# ESP32-EDU-BOARD_V0_1.net
KiCad netlist of a schematic drawn in EasyEDA
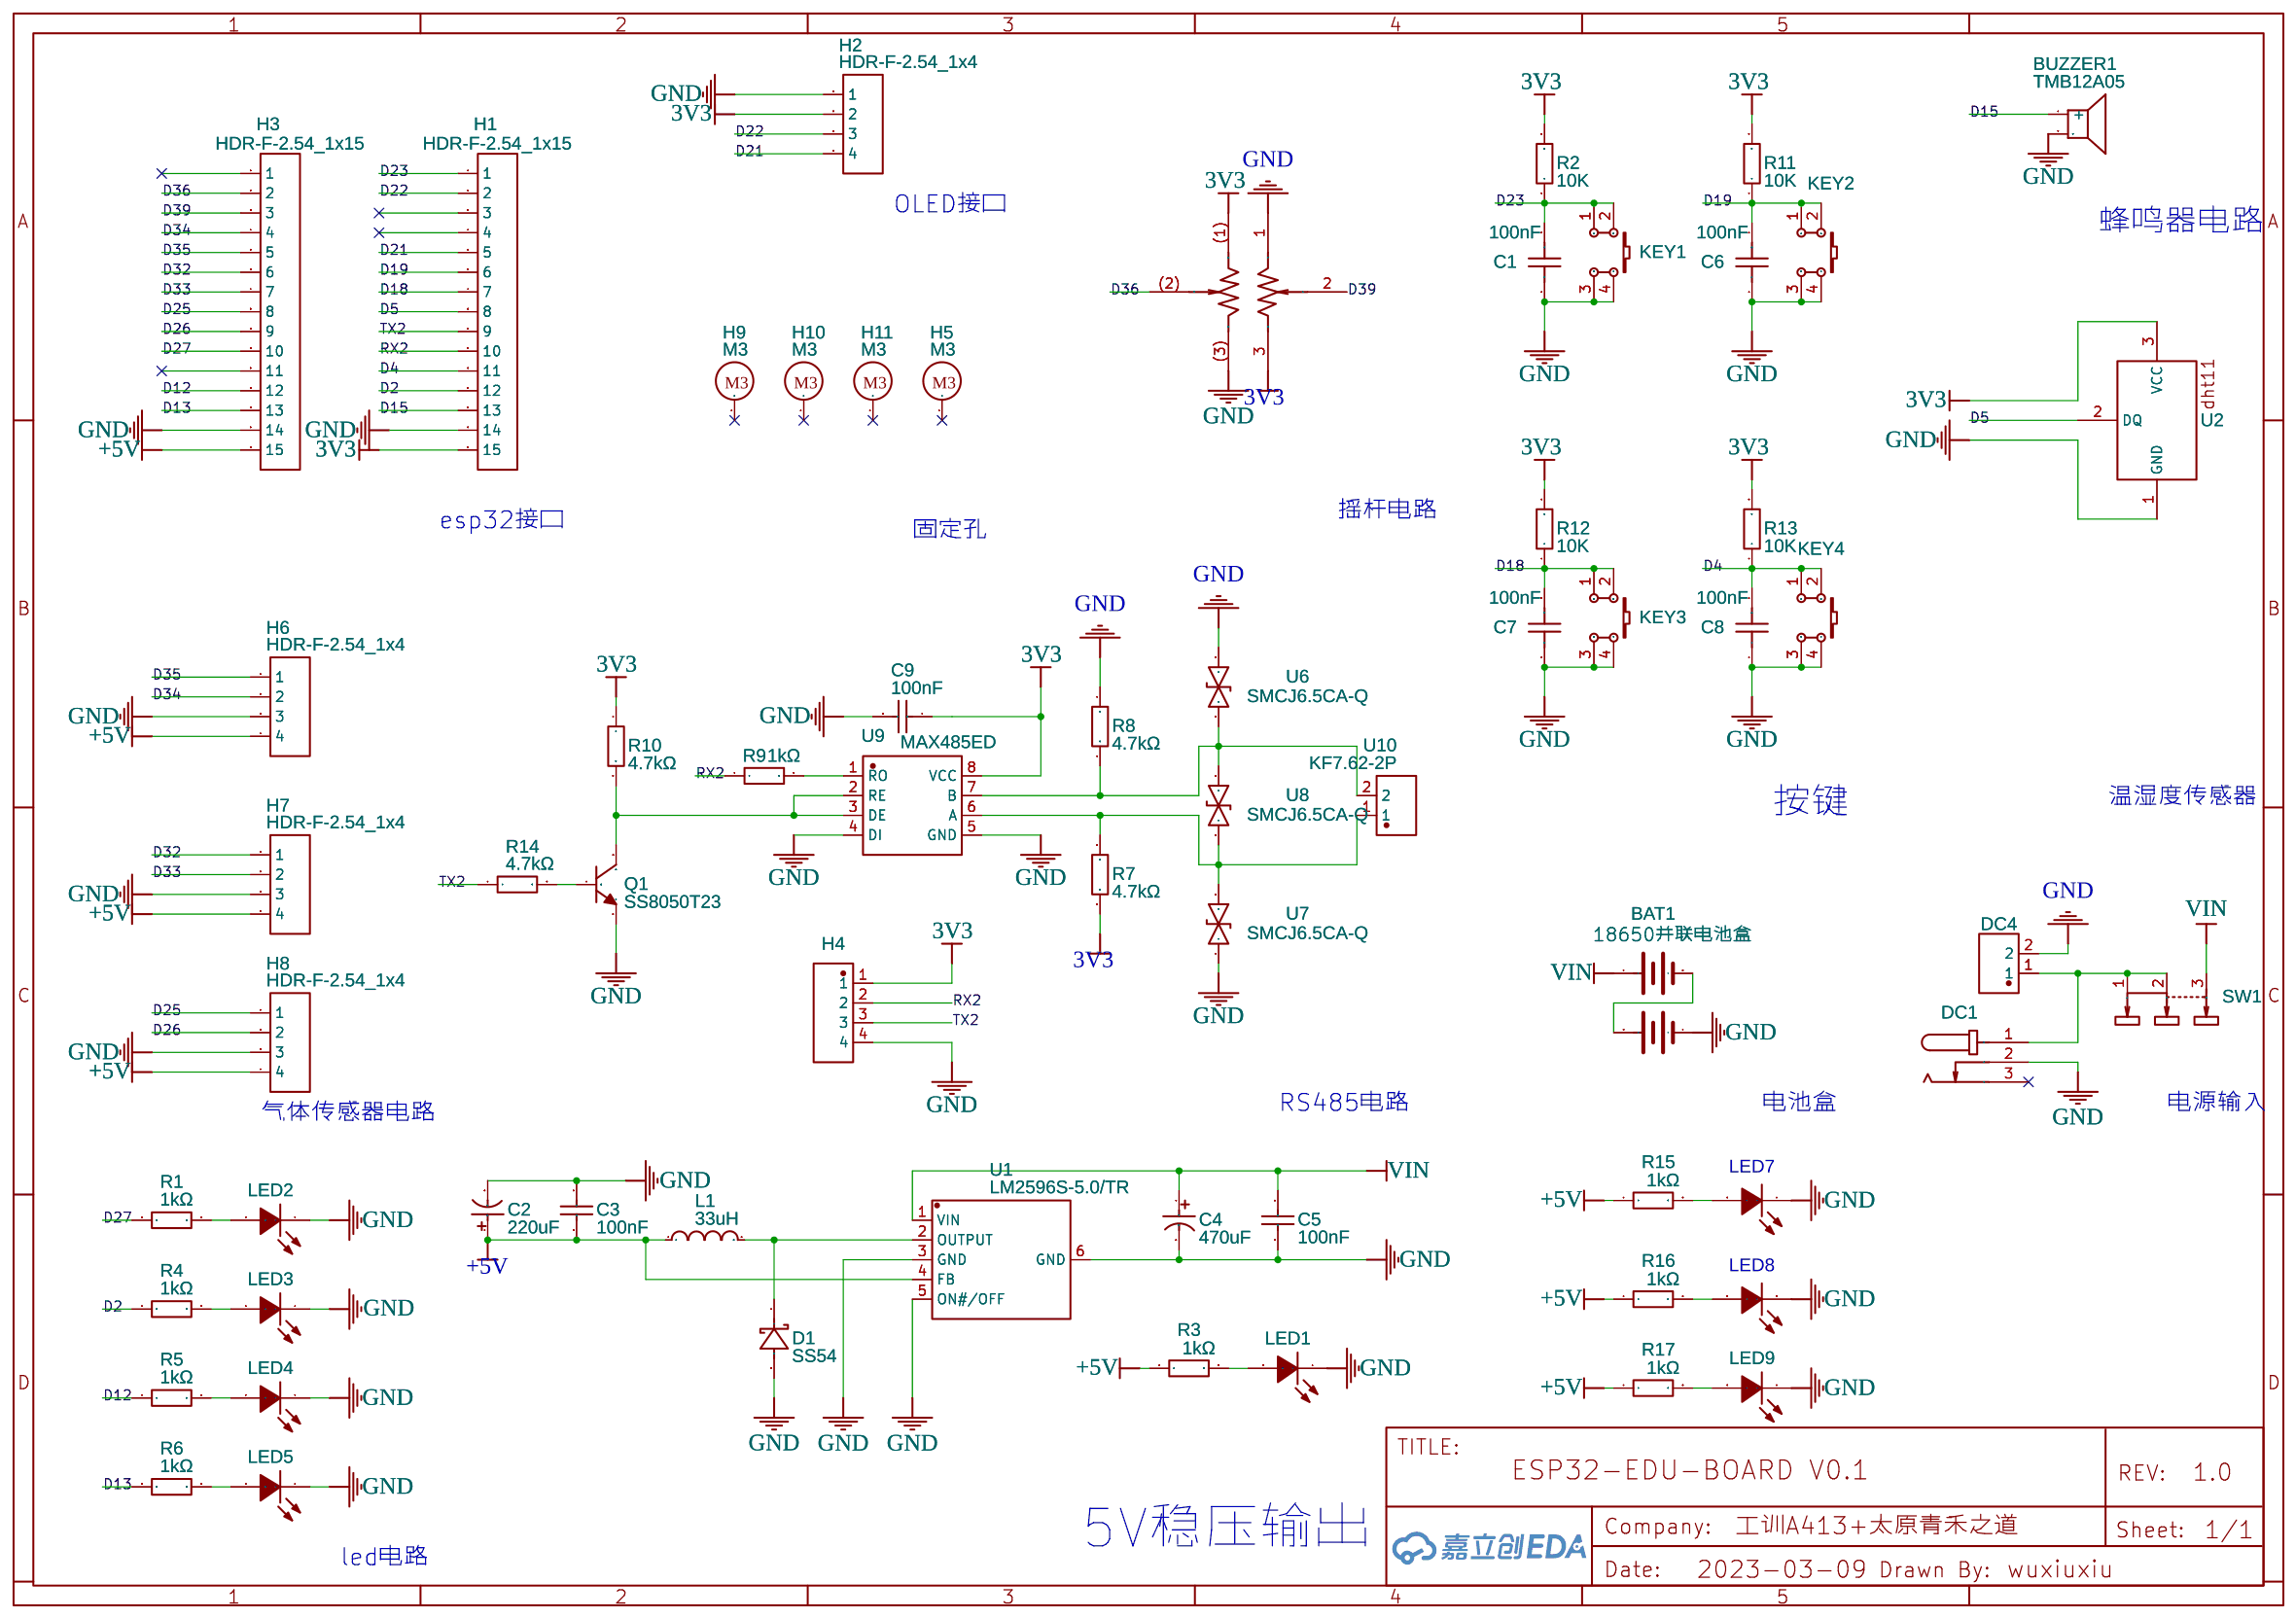
[diagram p0: schematic sheet]

(export (version "E")
  (design (tool "Eeschema 10.0.6"))
  (components
    (comp (ref "BAT1")
      (value "18650并联电池盒")
      (fields (field (name "BOM_Supplier Part") "C9900010344"))
      (libsource (lib "") (part "18650并联电池盒"))
    )
    (comp (ref "BUZZER1")
      (value "TMB12A05")
      (fields (field (name "BOM_Supplier Part") "C96093"))
      (libsource (lib "") (part "TMB12A05"))
    )
    (comp (ref "C1")
      (value "100nF")
      (fields
        (field (name "BOM_Manufacturer Part") "CC0603KRX7R9BB104")
        (field (name "BOM_Supplier Part") "C14663")
      )
      (libsource (lib "") (part "CC0603KRX7R9BB104"))
    )
    (comp (ref "C2")
      (value "220uF")
      (fields
        (field (name "BOM_Manufacturer Part") "RT1A221M0605")
        (field (name "BOM_Supplier Part") "C267466")
      )
      (libsource (lib "") (part "RT1A221M0605"))
    )
    (comp (ref "C3")
      (value "100nF")
      (fields
        (field (name "BOM_Manufacturer Part") "CL21B104KBCNNNC")
        (field (name "BOM_Supplier Part") "C1711")
      )
      (libsource (lib "") (part "CL21B104KBCNNNC_1"))
    )
    (comp (ref "C4")
      (value "470uF")
      (fields
        (field (name "BOM_Manufacturer Part") "RVE1C471M0810")
        (field (name "BOM_Supplier Part") "C107396")
      )
      (libsource (lib "") (part "RVE1C471M0810"))
    )
    (comp (ref "C5")
      (value "100nF")
      (fields
        (field (name "BOM_Manufacturer Part") "CL21B104KBCNNNC")
        (field (name "BOM_Supplier Part") "C1711")
      )
      (libsource (lib "") (part "CL21B104KBCNNNC_1"))
    )
    (comp (ref "C6")
      (value "100nF")
      (fields
        (field (name "BOM_Manufacturer Part") "CC0603KRX7R9BB104")
        (field (name "BOM_Supplier Part") "C14663")
      )
      (libsource (lib "") (part "CC0603KRX7R9BB104"))
    )
    (comp (ref "C7")
      (value "100nF")
      (fields
        (field (name "BOM_Manufacturer Part") "CC0603KRX7R9BB104")
        (field (name "BOM_Supplier Part") "C14663")
      )
      (libsource (lib "") (part "CC0603KRX7R9BB104"))
    )
    (comp (ref "C8")
      (value "100nF")
      (fields
        (field (name "BOM_Manufacturer Part") "CC0603KRX7R9BB104")
        (field (name "BOM_Supplier Part") "C14663")
      )
      (libsource (lib "") (part "CC0603KRX7R9BB104"))
    )
    (comp (ref "C9")
      (value "100nF")
      (fields
        (field (name "BOM_Manufacturer Part") "CL21B104KBCNNNC")
        (field (name "BOM_Supplier Part") "C1711")
      )
      (libsource (lib "") (part "CL21B104KBCNNNC"))
    )
    (comp (ref "D1")
      (value "SS54")
      (fields (field (name "BOM_Supplier Part") "C727065"))
      (libsource (lib "") (part "SS54_C727065"))
    )
    (comp (ref "DC1")
      (value "KH-DC-005-2.5")
      (fields (field (name "BOM_Supplier Part") "C2847170"))
      (libsource (lib "") (part "KH-DC-005-2.5"))
    )
    (comp (ref "DC4")
      (value "KF301-5.0-2P")
      (fields (field (name "BOM_Supplier Part") "C474881"))
      (libsource (lib "") (part "KF301-5.0-2P"))
    )
    (comp (ref "H1")
      (value "HDR-F-2.54_1x15")
      (fields (field (name "BOM_Supplier Part") "C124408"))
      (libsource (lib "") (part "HDR-F-2.54_1x15"))
    )
    (comp (ref "H2")
      (value "HDR-F-2.54_1x4")
      (fields (field (name "BOM_Supplier Part") "C225501"))
      (libsource (lib "") (part "HDR-F-2.54_1x4"))
    )
    (comp (ref "H3")
      (value "HDR-F-2.54_1x15")
      (fields (field (name "BOM_Supplier Part") "C124408"))
      (libsource (lib "") (part "HDR-F-2.54_1x15"))
    )
    (comp (ref "H4")
      (value "12251104CNSNS295001")
      (fields (field (name "BOM_Supplier Part") "C355292"))
      (libsource (lib "") (part "12251104CNSNS295001"))
    )
    (comp (ref "H5") (value "M3") (libsource (lib "") (part "M3")))
    (comp (ref "H6")
      (value "HDR-F-2.54_1x4")
      (fields (field (name "BOM_Supplier Part") "C225501"))
      (libsource (lib "") (part "HDR-F-2.54_1x4"))
    )
    (comp (ref "H7")
      (value "HDR-F-2.54_1x4")
      (fields (field (name "BOM_Supplier Part") "C225501"))
      (libsource (lib "") (part "HDR-F-2.54_1x4"))
    )
    (comp (ref "H8")
      (value "HDR-F-2.54_1x4")
      (fields (field (name "BOM_Supplier Part") "C225501"))
      (libsource (lib "") (part "HDR-F-2.54_1x4"))
    )
    (comp (ref "H9") (value "M3") (libsource (lib "") (part "M3")))
    (comp (ref "H10") (value "M3") (libsource (lib "") (part "M3")))
    (comp (ref "H11") (value "M3") (libsource (lib "") (part "M3")))
    (comp (ref "KEY1")
      (value "K4-6×6_SMD")
      (fields
        (field (name "BOM_Manufacturer Part") "K2-6639SP-D4SC-04")
        (field (name "BOM_Supplier Part") "C191626")
      )
      (libsource (lib "") (part "K4-6×6_SMD"))
    )
    (comp (ref "KEY2")
      (value "K4-6×6_SMD")
      (fields
        (field (name "BOM_Manufacturer Part") "K2-6639SP-D4SC-04")
        (field (name "BOM_Supplier Part") "C191626")
      )
      (libsource (lib "") (part "K4-6×6_SMD"))
    )
    (comp (ref "KEY3")
      (value "K4-6×6_SMD")
      (fields
        (field (name "BOM_Manufacturer Part") "K2-6639SP-D4SC-04")
        (field (name "BOM_Supplier Part") "C191626")
      )
      (libsource (lib "") (part "K4-6×6_SMD"))
    )
    (comp (ref "KEY4")
      (value "K4-6×6_SMD")
      (fields
        (field (name "BOM_Manufacturer Part") "K2-6639SP-D4SC-04")
        (field (name "BOM_Supplier Part") "C191626")
      )
      (libsource (lib "") (part "K4-6×6_SMD"))
    )
    (comp (ref "L1")
      (value "33uH")
      (fields
        (field (name "BOM_Manufacturer Part") "SLH1207S330MTT")
        (field (name "BOM_Supplier Part") "C181844")
      )
      (libsource (lib "") (part "SLH1207S330MTT"))
    )
    (comp (ref "LED1")
      (value "FC-2012HRK-620D")
      (fields (field (name "BOM_Supplier Part") "C84256"))
      (libsource (lib "") (part "FC-2012HRK-620D"))
    )
    (comp (ref "LED2")
      (value "FC-2012HRK-620D")
      (fields (field (name "BOM_Supplier Part") "C84256"))
      (libsource (lib "") (part "FC-2012HRK-620D"))
    )
    (comp (ref "LED3")
      (value "FC-2012HRK-620D")
      (fields (field (name "BOM_Supplier Part") "C84256"))
      (libsource (lib "") (part "FC-2012HRK-620D"))
    )
    (comp (ref "LED4")
      (value "FC-2012HRK-620D")
      (fields (field (name "BOM_Supplier Part") "C84256"))
      (libsource (lib "") (part "FC-2012HRK-620D"))
    )
    (comp (ref "LED5")
      (value "FC-2012HRK-620D")
      (fields (field (name "BOM_Supplier Part") "C84256"))
      (libsource (lib "") (part "FC-2012HRK-620D"))
    )
    (comp (ref "LED7")
      (value "FC-2012HRK-620D")
      (fields (field (name "BOM_Supplier Part") "C84256"))
      (libsource (lib "") (part "FC-2012HRK-620D"))
    )
    (comp (ref "LED8")
      (value "FC-2012HRK-620D")
      (fields (field (name "BOM_Supplier Part") "C84256"))
      (libsource (lib "") (part "FC-2012HRK-620D"))
    )
    (comp (ref "LED9")
      (value "FC-2012HRK-620D")
      (fields (field (name "BOM_Supplier Part") "C84256"))
      (libsource (lib "") (part "FC-2012HRK-620D"))
    )
    (comp (ref "Q1")
      (value "SS8050T23")
      (fields (field (name "BOM_Supplier Part") "C2939671"))
      (libsource (lib "") (part "SS8050T23"))
    )
    (comp (ref "R1")
      (value "1kΩ")
      (fields
        (field (name "BOM_Manufacturer Part") "RS-05K102JT")
        (field (name "BOM_Supplier Part") "C115302")
      )
      (libsource (lib "") (part "RS-05K102JT"))
    )
    (comp (ref "R2")
      (value "10K")
      (fields
        (field (name "BOM_Manufacturer Part") "0603WAF1002T5E")
        (field (name "BOM_Supplier Part") "C25804")
      )
      (libsource (lib "") (part "0603WAF1002T5E"))
    )
    (comp (ref "R3")
      (value "1kΩ")
      (fields
        (field (name "BOM_Manufacturer Part") "RS-05K102JT")
        (field (name "BOM_Supplier Part") "C115302")
      )
      (libsource (lib "") (part "RS-05K102JT"))
    )
    (comp (ref "R4")
      (value "1kΩ")
      (fields
        (field (name "BOM_Manufacturer Part") "RS-05K102JT")
        (field (name "BOM_Supplier Part") "C115302")
      )
      (libsource (lib "") (part "RS-05K102JT"))
    )
    (comp (ref "R5")
      (value "1kΩ")
      (fields
        (field (name "BOM_Manufacturer Part") "RS-05K102JT")
        (field (name "BOM_Supplier Part") "C115302")
      )
      (libsource (lib "") (part "RS-05K102JT"))
    )
    (comp (ref "R6")
      (value "1kΩ")
      (fields
        (field (name "BOM_Manufacturer Part") "RS-05K102JT")
        (field (name "BOM_Supplier Part") "C115302")
      )
      (libsource (lib "") (part "RS-05K102JT"))
    )
    (comp (ref "R7")
      (value "4.7kΩ")
      (fields
        (field (name "BOM_Manufacturer Part") "PTFR0805B4K70N9")
        (field (name "BOM_Supplier Part") "C328444")
      )
      (libsource (lib "") (part "PTFR0805B4K70N9"))
    )
    (comp (ref "R8")
      (value "4.7kΩ")
      (fields
        (field (name "BOM_Manufacturer Part") "PTFR0805B4K70N9")
        (field (name "BOM_Supplier Part") "C328444")
      )
      (libsource (lib "") (part "PTFR0805B4K70N9"))
    )
    (comp (ref "R9")
      (value "1kΩ")
      (fields
        (field (name "BOM_Manufacturer Part") "PTFR0805B1K00N9")
        (field (name "BOM_Supplier Part") "C328437")
      )
      (libsource (lib "") (part "PTFR0805B1K00N9"))
    )
    (comp (ref "R10")
      (value "4.7kΩ")
      (fields
        (field (name "BOM_Manufacturer Part") "PTFR0805B4K70N9")
        (field (name "BOM_Supplier Part") "C328444")
      )
      (libsource (lib "") (part "PTFR0805B4K70N9"))
    )
    (comp (ref "R11")
      (value "10K")
      (fields
        (field (name "BOM_Manufacturer Part") "0603WAF1002T5E")
        (field (name "BOM_Supplier Part") "C25804")
      )
      (libsource (lib "") (part "0603WAF1002T5E"))
    )
    (comp (ref "R12")
      (value "10K")
      (fields
        (field (name "BOM_Manufacturer Part") "0603WAF1002T5E")
        (field (name "BOM_Supplier Part") "C25804")
      )
      (libsource (lib "") (part "0603WAF1002T5E"))
    )
    (comp (ref "R13")
      (value "10K")
      (fields
        (field (name "BOM_Manufacturer Part") "0603WAF1002T5E")
        (field (name "BOM_Supplier Part") "C25804")
      )
      (libsource (lib "") (part "0603WAF1002T5E"))
    )
    (comp (ref "R14")
      (value "4.7kΩ")
      (fields
        (field (name "BOM_Manufacturer Part") "PTFR0805B4K70N9")
        (field (name "BOM_Supplier Part") "C328444")
      )
      (libsource (lib "") (part "PTFR0805B4K70N9_1"))
    )
    (comp (ref "R15")
      (value "1kΩ")
      (fields
        (field (name "BOM_Manufacturer Part") "RS-05K102JT")
        (field (name "BOM_Supplier Part") "C115302")
      )
      (libsource (lib "") (part "RS-05K102JT"))
    )
    (comp (ref "R16")
      (value "1kΩ")
      (fields
        (field (name "BOM_Manufacturer Part") "RS-05K102JT")
        (field (name "BOM_Supplier Part") "C115302")
      )
      (libsource (lib "") (part "RS-05K102JT"))
    )
    (comp (ref "R17")
      (value "1kΩ")
      (fields
        (field (name "BOM_Manufacturer Part") "RS-05K102JT")
        (field (name "BOM_Supplier Part") "C115302")
      )
      (libsource (lib "") (part "RS-05K102JT"))
    )
    (comp (ref "SW1")
      (value "SS-12D10L3")
      (fields (field (name "BOM_Supplier Part") "C319013"))
      (libsource (lib "") (part "SS-12D10L3"))
    )
    (comp (ref "SW2")
      (value "摇杆电位器 4方向 16*16 COPY COPY")
      (fields (field (name "BOM_Manufacturer Part") "3D161") (field (name "BOM_Supplier Part") "C92593"))
      (libsource (lib "") (part "摇杆电位器 4方向 16*16 COPY COPY"))
    )
    (comp (ref "U1")
      (value "LM2596S-5.0/TR")
      (fields (field (name "BOM_Supplier Part") "C194349"))
      (libsource (lib "") (part "LM2596S-5.0/TR"))
    )
    (comp (ref "U2") (value "华为牛逼3") (libsource (lib "") (part "华为牛逼3")))
    (comp (ref "U6")
      (value "SMCJ6.5CA-Q")
      (fields (field (name "BOM_Supplier Part") "C1517967"))
      (libsource (lib "") (part "SMCJ6.5CA-Q"))
    )
    (comp (ref "U7")
      (value "SMCJ6.5CA-Q")
      (fields (field (name "BOM_Supplier Part") "C1517967"))
      (libsource (lib "") (part "SMCJ6.5CA-Q"))
    )
    (comp (ref "U8")
      (value "SMCJ6.5CA-Q")
      (fields (field (name "BOM_Supplier Part") "C1517967"))
      (libsource (lib "") (part "SMCJ6.5CA-Q"))
    )
    (comp (ref "U9")
      (value "MAX485ED")
      (fields (field (name "BOM_Supplier Part") "C481667"))
      (libsource (lib "") (part "MAX485ED"))
    )
    (comp (ref "U10")
      (value "KF7.62-2P")
      (fields (field (name "BOM_Supplier Part") "C707824"))
      (libsource (lib "") (part "KF7.62-2P"))
    )
  )
  (nets
    (net (code "1") (name "+5V") (class "Default")
      (node (ref "C2") (pin "1") (pinfunction "1_1") (pintype "input"))
      (node (ref "C3") (pin "1") (pinfunction "1_1") (pintype "input"))
      (node (ref "H3") (pin "15") (pinfunction "15_15") (pintype "unspecified"))
      (node (ref "H6") (pin "4") (pinfunction "4_4") (pintype "unspecified"))
      (node (ref "H7") (pin "4") (pinfunction "4_4") (pintype "unspecified"))
      (node (ref "H8") (pin "4") (pinfunction "4_4") (pintype "unspecified"))
      (node (ref "L1") (pin "1") (pinfunction "1_1") (pintype "unspecified"))
      (node (ref "R15") (pin "1") (pinfunction "1_1") (pintype "input"))
      (node (ref "R16") (pin "1") (pinfunction "1_1") (pintype "input"))
      (node (ref "R17") (pin "1") (pinfunction "1_1") (pintype "input"))
      (node (ref "R3") (pin "1") (pinfunction "1_1") (pintype "input"))
      (node (ref "U1") (pin "4") (pinfunction "FB_4") (pintype "unspecified"))
    )
    (net (code "2") (name "/D2") (class "Default")
      (node (ref "H1") (pin "12") (pinfunction "12_12") (pintype "unspecified"))
      (node (ref "R4") (pin "1") (pinfunction "1_1") (pintype "input"))
    )
    (net (code "3") (name "/D4") (class "Default")
      (node (ref "C8") (pin "2") (pinfunction "2_2") (pintype "unspecified"))
      (node (ref "H1") (pin "11") (pinfunction "11_11") (pintype "unspecified"))
      (node (ref "KEY4") (pin "1") (pinfunction "1_1") (pintype "unspecified"))
      (node (ref "KEY4") (pin "2") (pinfunction "2_2") (pintype "unspecified"))
      (node (ref "R13") (pin "1") (pinfunction "1_1") (pintype "input"))
    )
    (net (code "4") (name "/D5") (class "Default")
      (node (ref "H1") (pin "8") (pinfunction "8_8") (pintype "unspecified"))
      (node (ref "U2") (pin "2") (pinfunction "DQ_2") (pintype "unspecified"))
    )
    (net (code "5") (name "/D12") (class "Default")
      (node (ref "H3") (pin "12") (pinfunction "12_12") (pintype "unspecified"))
      (node (ref "R5") (pin "1") (pinfunction "1_1") (pintype "input"))
    )
    (net (code "6") (name "/D13") (class "Default")
      (node (ref "H3") (pin "13") (pinfunction "13_13") (pintype "unspecified"))
      (node (ref "R6") (pin "1") (pinfunction "1_1") (pintype "input"))
    )
    (net (code "7") (name "/D15") (class "Default")
      (node (ref "BUZZER1") (pin "1") (pinfunction "+_1") (pintype "unspecified"))
      (node (ref "H1") (pin "13") (pinfunction "13_13") (pintype "unspecified"))
    )
    (net (code "8") (name "/D18") (class "Default")
      (node (ref "C7") (pin "2") (pinfunction "2_2") (pintype "unspecified"))
      (node (ref "H1") (pin "7") (pinfunction "7_7") (pintype "unspecified"))
      (node (ref "KEY3") (pin "1") (pinfunction "1_1") (pintype "unspecified"))
      (node (ref "KEY3") (pin "2") (pinfunction "2_2") (pintype "unspecified"))
      (node (ref "R12") (pin "1") (pinfunction "1_1") (pintype "input"))
    )
    (net (code "9") (name "/D19") (class "Default")
      (node (ref "C6") (pin "2") (pinfunction "2_2") (pintype "unspecified"))
      (node (ref "H1") (pin "6") (pinfunction "6_6") (pintype "unspecified"))
      (node (ref "KEY2") (pin "1") (pinfunction "1_1") (pintype "unspecified"))
      (node (ref "KEY2") (pin "2") (pinfunction "2_2") (pintype "unspecified"))
      (node (ref "R11") (pin "1") (pinfunction "1_1") (pintype "input"))
    )
    (net (code "10") (name "/D21") (class "Default")
      (node (ref "H1") (pin "5") (pinfunction "5_5") (pintype "unspecified"))
      (node (ref "H2") (pin "4") (pinfunction "4_4") (pintype "unspecified"))
    )
    (net (code "11") (name "/D22") (class "Default")
      (node (ref "H1") (pin "2") (pinfunction "2_2") (pintype "unspecified"))
      (node (ref "H2") (pin "3") (pinfunction "3_3") (pintype "unspecified"))
    )
    (net (code "12") (name "/D23") (class "Default")
      (node (ref "C1") (pin "2") (pinfunction "2_2") (pintype "unspecified"))
      (node (ref "H1") (pin "1") (pinfunction "1_1") (pintype "unspecified"))
      (node (ref "KEY1") (pin "1") (pinfunction "1_1") (pintype "unspecified"))
      (node (ref "KEY1") (pin "2") (pinfunction "2_2") (pintype "unspecified"))
      (node (ref "R2") (pin "1") (pinfunction "1_1") (pintype "input"))
    )
    (net (code "13") (name "/D25") (class "Default")
      (node (ref "H3") (pin "8") (pinfunction "8_8") (pintype "unspecified"))
      (node (ref "H8") (pin "1") (pinfunction "1_1") (pintype "unspecified"))
    )
    (net (code "14") (name "/D26") (class "Default")
      (node (ref "H3") (pin "9") (pinfunction "9_9") (pintype "unspecified"))
      (node (ref "H8") (pin "2") (pinfunction "2_2") (pintype "unspecified"))
    )
    (net (code "15") (name "/D27") (class "Default")
      (node (ref "H3") (pin "10") (pinfunction "10_10") (pintype "unspecified"))
      (node (ref "R1") (pin "1") (pinfunction "1_1") (pintype "input"))
    )
    (net (code "16") (name "/D32") (class "Default")
      (node (ref "H3") (pin "6") (pinfunction "6_6") (pintype "unspecified"))
      (node (ref "H7") (pin "1") (pinfunction "1_1") (pintype "unspecified"))
    )
    (net (code "17") (name "/D33") (class "Default")
      (node (ref "H3") (pin "7") (pinfunction "7_7") (pintype "unspecified"))
      (node (ref "H7") (pin "2") (pinfunction "2_2") (pintype "unspecified"))
    )
    (net (code "18") (name "/D34") (class "Default")
      (node (ref "H3") (pin "4") (pinfunction "4_4") (pintype "unspecified"))
      (node (ref "H6") (pin "2") (pinfunction "2_2") (pintype "unspecified"))
    )
    (net (code "19") (name "/D35") (class "Default")
      (node (ref "H3") (pin "5") (pinfunction "5_5") (pintype "unspecified"))
      (node (ref "H6") (pin "1") (pinfunction "1_1") (pintype "unspecified"))
    )
    (net (code "20") (name "/D36") (class "Default")
      (node (ref "H3") (pin "2") (pinfunction "2_2") (pintype "unspecified"))
      (node (ref "SW2") (pin "(2)") (pinfunction "(2)_(2)") (pintype "unspecified"))
    )
    (net (code "21") (name "/D39") (class "Default")
      (node (ref "H3") (pin "3") (pinfunction "3_3") (pintype "unspecified"))
      (node (ref "SW2") (pin "2") (pinfunction "2_2") (pintype "unspecified"))
    )
    (net (code "22") (name "/RX2") (class "Default")
      (node (ref "H1") (pin "10") (pinfunction "10_10") (pintype "unspecified"))
      (node (ref "H4") (pin "2") (pinfunction "2_2") (pintype "unspecified"))
      (node (ref "R9") (pin "1") (pinfunction "1_1") (pintype "unspecified"))
    )
    (net (code "23") (name "/TX2") (class "Default")
      (node (ref "H1") (pin "9") (pinfunction "9_9") (pintype "unspecified"))
      (node (ref "H4") (pin "3") (pinfunction "3_3") (pintype "unspecified"))
      (node (ref "R14") (pin "1") (pinfunction "1_1") (pintype "unspecified"))
    )
    (net (code "24") (name "3V3") (class "Default")
      (node (ref "C9") (pin "1") (pinfunction "1_1") (pintype "input"))
      (node (ref "H1") (pin "15") (pinfunction "15_15") (pintype "unspecified"))
      (node (ref "H2") (pin "2") (pinfunction "2_2") (pintype "unspecified"))
      (node (ref "H4") (pin "1") (pinfunction "1_1") (pintype "unspecified"))
      (node (ref "R10") (pin "1") (pinfunction "1_1") (pintype "unspecified"))
      (node (ref "R11") (pin "2") (pinfunction "2_2") (pintype "input"))
      (node (ref "R12") (pin "2") (pinfunction "2_2") (pintype "input"))
      (node (ref "R13") (pin "2") (pinfunction "2_2") (pintype "input"))
      (node (ref "R2") (pin "2") (pinfunction "2_2") (pintype "input"))
      (node (ref "R7") (pin "2") (pinfunction "2_2") (pintype "unspecified"))
      (node (ref "SW2") (pin "(1)") (pinfunction "(1)_(1)") (pintype "unspecified"))
      (node (ref "SW2") (pin "3") (pinfunction "3_3") (pintype "unspecified"))
      (node (ref "U2") (pin "3") (pinfunction "VCC_3") (pintype "unspecified"))
      (node (ref "U9") (pin "8") (pinfunction "VCC_8") (pintype "unspecified"))
    )
    (net (code "25") (name "GND") (class "Default")
      (node (ref "BAT1") (pin "4") (pinfunction "-_4") (pintype "passive"))
      (node (ref "BUZZER1") (pin "2") (pinfunction "2_2") (pintype "unspecified"))
      (node (ref "C1") (pin "1") (pinfunction "1_1") (pintype "unspecified"))
      (node (ref "C2") (pin "2") (pinfunction "2_2") (pintype "input"))
      (node (ref "C3") (pin "2") (pinfunction "2_2") (pintype "input"))
      (node (ref "C4") (pin "2") (pinfunction "2_2") (pintype "input"))
      (node (ref "C5") (pin "1") (pinfunction "1_1") (pintype "input"))
      (node (ref "C6") (pin "1") (pinfunction "1_1") (pintype "unspecified"))
      (node (ref "C7") (pin "1") (pinfunction "1_1") (pintype "unspecified"))
      (node (ref "C8") (pin "1") (pinfunction "1_1") (pintype "unspecified"))
      (node (ref "C9") (pin "2") (pinfunction "2_2") (pintype "input"))
      (node (ref "D1") (pin "2") (pinfunction "2_2") (pintype "unspecified"))
      (node (ref "DC1") (pin "2") (pinfunction "2_2") (pintype "unspecified"))
      (node (ref "DC4") (pin "2") (pinfunction "2_2") (pintype "unspecified"))
      (node (ref "H1") (pin "14") (pinfunction "14_14") (pintype "unspecified"))
      (node (ref "H2") (pin "1") (pinfunction "1_1") (pintype "unspecified"))
      (node (ref "H3") (pin "14") (pinfunction "14_14") (pintype "unspecified"))
      (node (ref "H4") (pin "4") (pinfunction "4_4") (pintype "unspecified"))
      (node (ref "H6") (pin "3") (pinfunction "3_3") (pintype "unspecified"))
      (node (ref "H7") (pin "3") (pinfunction "3_3") (pintype "unspecified"))
      (node (ref "H8") (pin "3") (pinfunction "3_3") (pintype "unspecified"))
      (node (ref "KEY1") (pin "3") (pinfunction "3_3") (pintype "unspecified"))
      (node (ref "KEY1") (pin "4") (pinfunction "4_4") (pintype "unspecified"))
      (node (ref "KEY2") (pin "3") (pinfunction "3_3") (pintype "unspecified"))
      (node (ref "KEY2") (pin "4") (pinfunction "4_4") (pintype "unspecified"))
      (node (ref "KEY3") (pin "3") (pinfunction "3_3") (pintype "unspecified"))
      (node (ref "KEY3") (pin "4") (pinfunction "4_4") (pintype "unspecified"))
      (node (ref "KEY4") (pin "3") (pinfunction "3_3") (pintype "unspecified"))
      (node (ref "KEY4") (pin "4") (pinfunction "4_4") (pintype "unspecified"))
      (node (ref "LED1") (pin "1") (pinfunction "-_1") (pintype "unspecified"))
      (node (ref "LED2") (pin "1") (pinfunction "-_1") (pintype "unspecified"))
      (node (ref "LED3") (pin "1") (pinfunction "-_1") (pintype "unspecified"))
      (node (ref "LED4") (pin "1") (pinfunction "-_1") (pintype "unspecified"))
      (node (ref "LED5") (pin "1") (pinfunction "-_1") (pintype "unspecified"))
      (node (ref "LED7") (pin "1") (pinfunction "-_1") (pintype "unspecified"))
      (node (ref "LED8") (pin "1") (pinfunction "-_1") (pintype "unspecified"))
      (node (ref "LED9") (pin "1") (pinfunction "-_1") (pintype "unspecified"))
      (node (ref "Q1") (pin "2") (pinfunction "E_2") (pintype "input"))
      (node (ref "R8") (pin "1") (pinfunction "1_1") (pintype "unspecified"))
      (node (ref "SW2") (pin "(3)") (pinfunction "(3)_(3)") (pintype "unspecified"))
      (node (ref "SW2") (pin "1") (pinfunction "1_1") (pintype "unspecified"))
      (node (ref "U1") (pin "3") (pinfunction "GND_3") (pintype "unspecified"))
      (node (ref "U1") (pin "5") (pinfunction "ON#/OFF_5") (pintype "unspecified"))
      (node (ref "U1") (pin "6") (pinfunction "GND_6") (pintype "unspecified"))
      (node (ref "U2") (pin "1") (pinfunction "GND_1") (pintype "unspecified"))
      (node (ref "U6") (pin "2") (pinfunction "A_2") (pintype "unspecified"))
      (node (ref "U7") (pin "1") (pinfunction "K_1") (pintype "unspecified"))
      (node (ref "U9") (pin "4") (pinfunction "DI_4") (pintype "unspecified"))
      (node (ref "U9") (pin "5") (pinfunction "GND_5") (pintype "unspecified"))
    )
    (net (code "26") (name "Net-(BAT1-+-Pad2)") (class "Default")
      (node (ref "BAT1") (pin "2") (pinfunction "+_2") (pintype "passive"))
      (node (ref "BAT1") (pin "3") (pinfunction "-_3") (pintype "passive"))
    )
    (net (code "27") (name "Net-(DC1-Pad1)") (class "Default")
      (node (ref "DC1") (pin "1") (pinfunction "1_1") (pintype "unspecified"))
      (node (ref "DC4") (pin "1") (pinfunction "1_1") (pintype "unspecified"))
      (node (ref "SW1") (pin "1") (pinfunction "1_1") (pintype "unspecified"))
      (node (ref "SW1") (pin "2") (pinfunction "2_2") (pintype "unspecified"))
    )
    (net (code "28") (name "Net-(LED1-+)") (class "Default")
      (node (ref "LED1") (pin "2") (pinfunction "+_2") (pintype "unspecified"))
      (node (ref "R3") (pin "2") (pinfunction "2_2") (pintype "input"))
    )
    (net (code "29") (name "Net-(LED2-+)") (class "Default")
      (node (ref "LED2") (pin "2") (pinfunction "+_2") (pintype "unspecified"))
      (node (ref "R1") (pin "2") (pinfunction "2_2") (pintype "input"))
    )
    (net (code "30") (name "Net-(LED3-+)") (class "Default")
      (node (ref "LED3") (pin "2") (pinfunction "+_2") (pintype "unspecified"))
      (node (ref "R4") (pin "2") (pinfunction "2_2") (pintype "input"))
    )
    (net (code "31") (name "Net-(LED4-+)") (class "Default")
      (node (ref "LED4") (pin "2") (pinfunction "+_2") (pintype "unspecified"))
      (node (ref "R5") (pin "2") (pinfunction "2_2") (pintype "input"))
    )
    (net (code "32") (name "Net-(LED5-+)") (class "Default")
      (node (ref "LED5") (pin "2") (pinfunction "+_2") (pintype "unspecified"))
      (node (ref "R6") (pin "2") (pinfunction "2_2") (pintype "input"))
    )
    (net (code "33") (name "Net-(LED7-+)") (class "Default")
      (node (ref "LED7") (pin "2") (pinfunction "+_2") (pintype "unspecified"))
      (node (ref "R15") (pin "2") (pinfunction "2_2") (pintype "input"))
    )
    (net (code "34") (name "Net-(LED8-+)") (class "Default")
      (node (ref "LED8") (pin "2") (pinfunction "+_2") (pintype "unspecified"))
      (node (ref "R16") (pin "2") (pinfunction "2_2") (pintype "input"))
    )
    (net (code "35") (name "Net-(LED9-+)") (class "Default")
      (node (ref "LED9") (pin "2") (pinfunction "+_2") (pintype "unspecified"))
      (node (ref "R17") (pin "2") (pinfunction "2_2") (pintype "input"))
    )
    (net (code "36") (name "Net-(Q1-B)") (class "Default")
      (node (ref "Q1") (pin "1") (pinfunction "B_1") (pintype "input"))
      (node (ref "R14") (pin "2") (pinfunction "2_2") (pintype "unspecified"))
    )
    (net (code "37") (name "Net-(Q1-C)") (class "Default")
      (node (ref "Q1") (pin "3") (pinfunction "C_3") (pintype "input"))
      (node (ref "R10") (pin "2") (pinfunction "2_2") (pintype "unspecified"))
      (node (ref "U9") (pin "2") (pinfunction "RE_2") (pintype "unspecified"))
      (node (ref "U9") (pin "3") (pinfunction "DE_3") (pintype "unspecified"))
    )
    (net (code "38") (name "Net-(U1-OUTPUT)") (class "Default")
      (node (ref "D1") (pin "1") (pinfunction "1_1") (pintype "unspecified"))
      (node (ref "L1") (pin "2") (pinfunction "2_2") (pintype "unspecified"))
      (node (ref "U1") (pin "2") (pinfunction "OUTPUT_2") (pintype "unspecified"))
    )
    (net (code "39") (name "Net-(U6-K)") (class "Default")
      (node (ref "R8") (pin "2") (pinfunction "2_2") (pintype "unspecified"))
      (node (ref "U10") (pin "2") (pinfunction "2_2") (pintype "unspecified"))
      (node (ref "U6") (pin "1") (pinfunction "K_1") (pintype "unspecified"))
      (node (ref "U8") (pin "2") (pinfunction "A_2") (pintype "unspecified"))
      (node (ref "U9") (pin "7") (pinfunction "B_7") (pintype "unspecified"))
    )
    (net (code "40") (name "Net-(U7-A)") (class "Default")
      (node (ref "R7") (pin "1") (pinfunction "1_1") (pintype "unspecified"))
      (node (ref "U10") (pin "1") (pinfunction "1_1") (pintype "unspecified"))
      (node (ref "U7") (pin "2") (pinfunction "A_2") (pintype "unspecified"))
      (node (ref "U8") (pin "1") (pinfunction "K_1") (pintype "unspecified"))
      (node (ref "U9") (pin "6") (pinfunction "A_6") (pintype "unspecified"))
    )
    (net (code "41") (name "Net-(U9-RO)") (class "Default")
      (node (ref "R9") (pin "2") (pinfunction "2_2") (pintype "unspecified"))
      (node (ref "U9") (pin "1") (pinfunction "RO_1") (pintype "unspecified"))
    )
    (net (code "42") (name "VIN") (class "Default")
      (node (ref "BAT1") (pin "1") (pinfunction "+_1") (pintype "passive"))
      (node (ref "C4") (pin "1") (pinfunction "1_1") (pintype "input"))
      (node (ref "C5") (pin "2") (pinfunction "2_2") (pintype "input"))
      (node (ref "SW1") (pin "3") (pinfunction "3_3") (pintype "unspecified"))
      (node (ref "U1") (pin "1") (pinfunction "VIN_1") (pintype "unspecified"))
    )
    (net (code "43") (name "unconnected-(DC1-Pad3)") (class "Default")
      (node (ref "DC1") (pin "3") (pinfunction "3_3") (pintype "unspecified+no_connect"))
    )
    (net (code "44") (name "unconnected-(H1-Pad3)") (class "Default")
      (node (ref "H1") (pin "3") (pinfunction "3_3") (pintype "unspecified+no_connect"))
    )
    (net (code "45") (name "unconnected-(H1-Pad4)") (class "Default")
      (node (ref "H1") (pin "4") (pinfunction "4_4") (pintype "unspecified+no_connect"))
    )
    (net (code "46") (name "unconnected-(H3-Pad1)") (class "Default")
      (node (ref "H3") (pin "1") (pinfunction "1_1") (pintype "unspecified+no_connect"))
    )
    (net (code "47") (name "unconnected-(H3-Pad11)") (class "Default")
      (node (ref "H3") (pin "11") (pinfunction "11_11") (pintype "unspecified+no_connect"))
    )
    (net (code "48") (name "unconnected-(H5-Pad1)") (class "Default")
      (node (ref "H5") (pin "1") (pinfunction "1_1") (pintype "unspecified+no_connect"))
    )
    (net (code "49") (name "unconnected-(H9-Pad1)") (class "Default")
      (node (ref "H9") (pin "1") (pinfunction "1_1") (pintype "unspecified+no_connect"))
    )
    (net (code "50") (name "unconnected-(H10-Pad1)") (class "Default")
      (node (ref "H10") (pin "1") (pinfunction "1_1") (pintype "unspecified+no_connect"))
    )
    (net (code "51") (name "unconnected-(H11-Pad1)") (class "Default")
      (node (ref "H11") (pin "1") (pinfunction "1_1") (pintype "unspecified+no_connect"))
    )
  )
)
